# INTERNAL_REGULATORS.net
KiCad netlist of a schematic drawn in Altium Designer
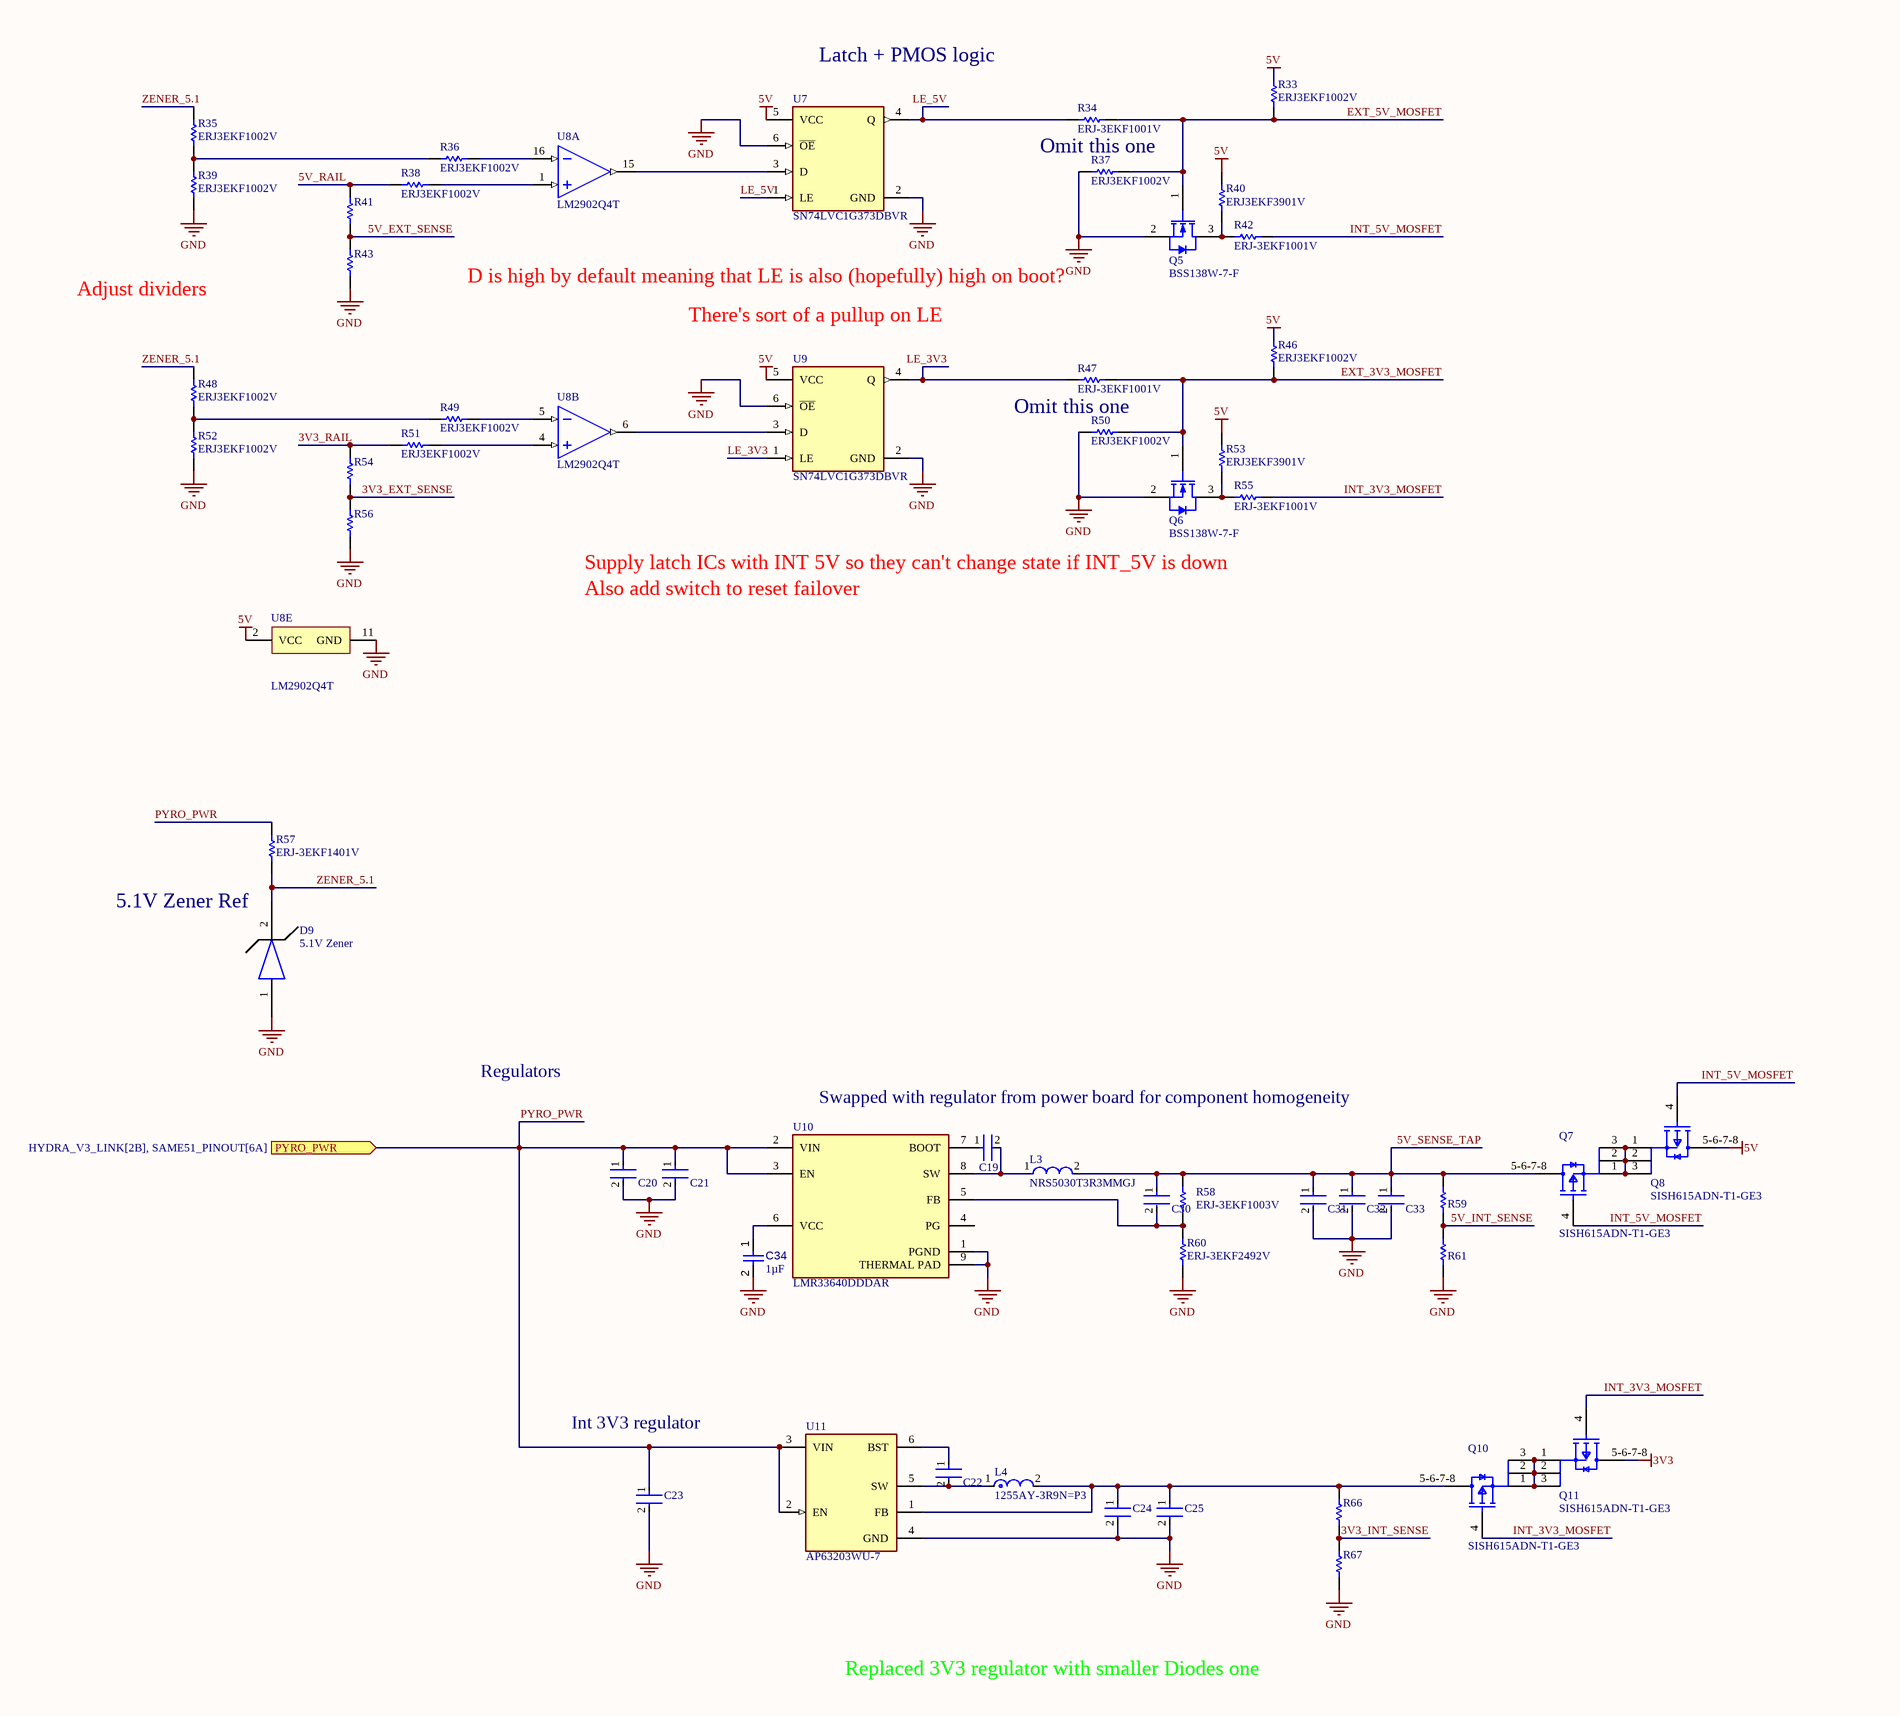
[diagram p0: INTERNAL_REGULATORS.SchDoc, left]
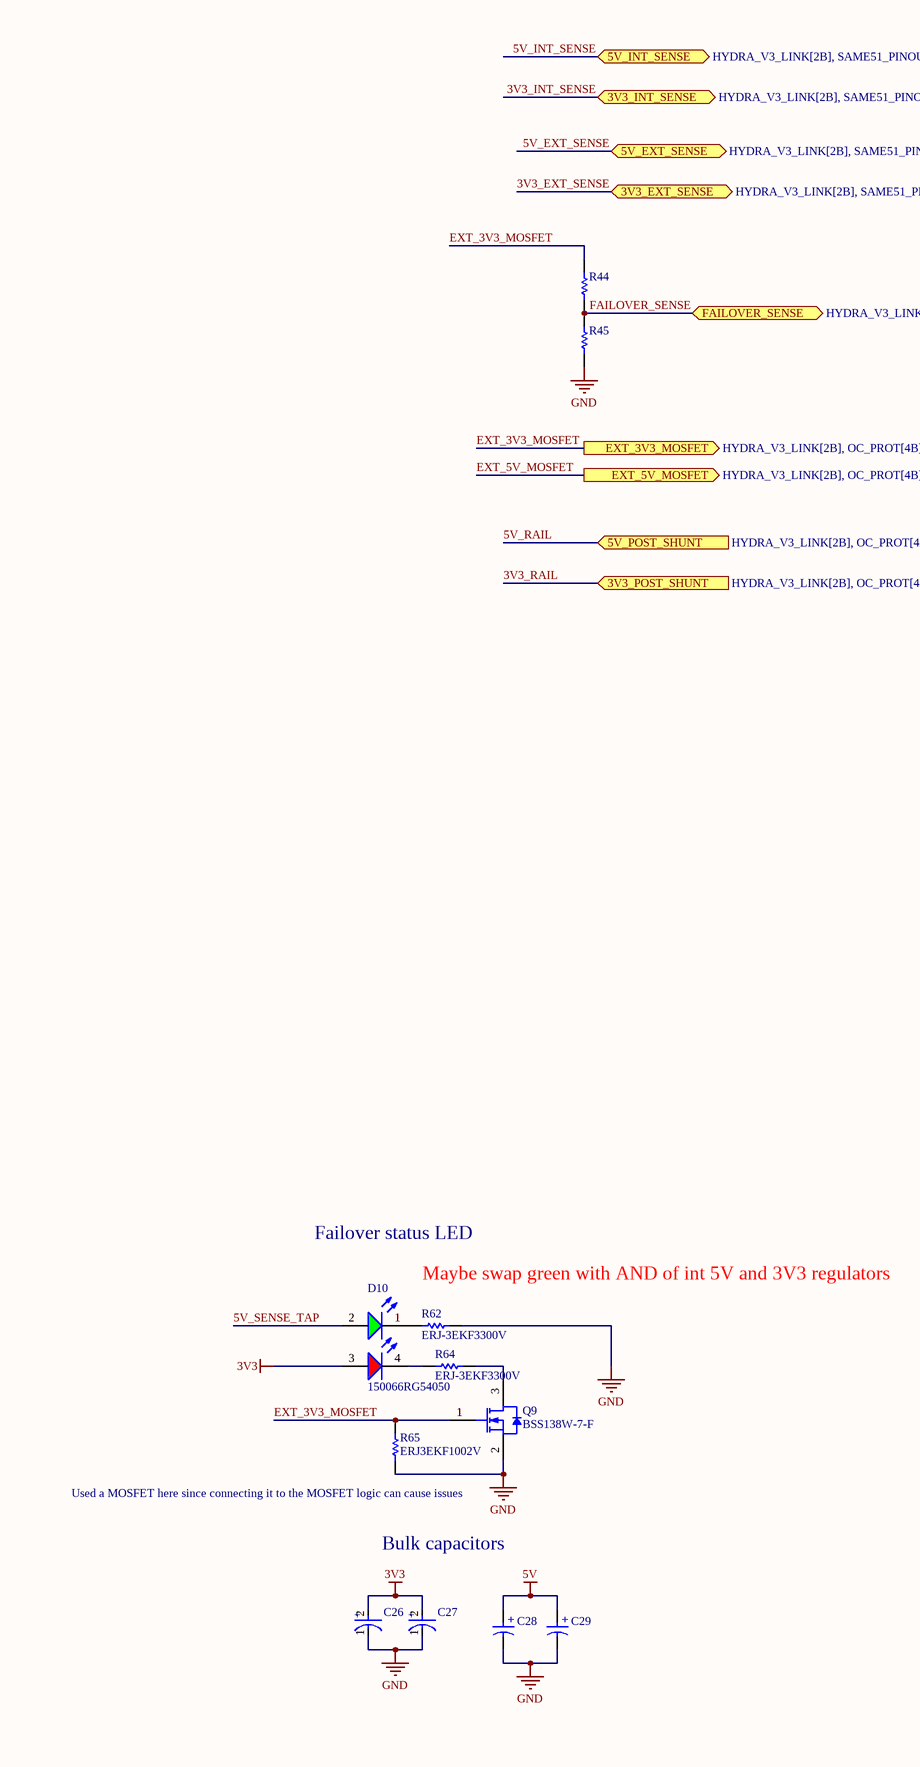
[diagram p1: INTERNAL_REGULATORS.SchDoc, right]

(export (version "E")
  (design (tool "Eeschema 10.0.6"))
  (components
    (comp (ref "C19")
      (value "C0402C104K8PACTU")
      (footprint "FP-C0402-BB-MFG")
      (description "CAP CER 0.1UF 10V X5R 0402")
      (fields (field (name "MANUFACTURER") "Kemet") (field (name "TOLERANCE") "0.1"))
      (libsource (lib "Altium Content Vault") (part "b4654b650e69147ec39a6b967a45e02"))
    )
    (comp (ref "C20")
      (value "CL10A106MA8NRNC")
      (footprint "FP-CL10-IPC_B")
      (libsource (lib "uORocketry Hardware") (part "b4654b650e69147ec39a6b967a45e02"))
    )
    (comp (ref "C21")
      (value "C0603C224M3RACTU")
      (footprint "FP-C0603C-CF-IPC_B")
      (libsource (lib "uORocketry Hardware") (part "b4654b650e69147ec39a6b967a45e02"))
    )
    (comp (ref "C22")
      (value "C0402C104K8PACTU")
      (footprint "FP-C0402-BB-MFG")
      (description "CAP CER 0.1UF 10V X5R 0402")
      (fields (field (name "MANUFACTURER") "Kemet") (field (name "TOLERANCE") "0.1"))
      (libsource (lib "Altium Content Vault") (part "b4654b650e69147ec39a6b967a45e02"))
    )
    (comp (ref "C23")
      (value "C0805C106K8PACTU")
      (footprint "FP-C0805C-DG-MFG")
      (description "CAP CER 10UF 10V X5R 0805")
      (fields (field (name "TOLERANCE") "10%") (field (name "MANUFACTURER") "Kemet"))
      (libsource (lib "Altium Content Vault") (part "11868f565c42a9108669ba33697ecf6"))
    )
    (comp (ref "C24")
      (value "GRM21BR61E226ME44L")
      (footprint "FP-GRM21B-0_2-e0_2_0_7-IPC_B")
      (description "Chip Multilayer Ceramic Capacitors for General Purpose, 0805, 22uF, X5R, 15%, 20%, 25V")
      (fields (field (name "TOLERANCE") "20%") (field (name "VOLTAGE") "25V"))
      (libsource (lib "Altium Content Vault") (part "b4654b650e69147ec39a6b967a45e02"))
    )
    (comp (ref "C25")
      (value "GRM21BR61E226ME44L")
      (footprint "FP-GRM21B-0_2-e0_2_0_7-IPC_B")
      (description "Chip Multilayer Ceramic Capacitors for General Purpose, 0805, 22uF, X5R, 15%, 20%, 25V")
      (fields (field (name "TOLERANCE") "20%") (field (name "VOLTAGE") "25V"))
      (libsource (lib "Altium Content Vault") (part "b4654b650e69147ec39a6b967a45e02"))
    )
    (comp (ref "C26")
      (value "6TPE120MAZB")
      (footprint "FP-POSCAP-B2-MFG")
      (description "Molded Tantalum Polymer Capacitor 120uF 20% 6.3V life 1000Hours SMD 1411")
      (fields (field (name "TOLERANCE") "20%") (field (name "VOLTAGE") "6.3V"))
      (libsource (lib "Altium Content Vault") (part "cf48714ba7e38822c1575c7ec0b6d1f"))
    )
    (comp (ref "C27")
      (value "6TPE120MAZB")
      (footprint "FP-POSCAP-B2-MFG")
      (description "Molded Tantalum Polymer Capacitor 120uF 20% 6.3V life 1000Hours SMD 1411")
      (fields (field (name "TOLERANCE") "20%") (field (name "VOLTAGE") "6.3V"))
      (libsource (lib "Altium Content Vault") (part "cf48714ba7e38822c1575c7ec0b6d1f"))
    )
    (comp (ref "C28")
      (value "875035119002")
      (footprint "WCAP-PHLE_L7.3W4.3H1.9")
      (description "875035119002 WCAP-PHLE Aluminum Polymer Capacitors")
      (libsource (lib "Altium Content Vault") (part "Capacitor_Polarized"))
    )
    (comp (ref "C29")
      (value "875035119002")
      (footprint "WCAP-PHLE_L7.3W4.3H1.9")
      (description "875035119002 WCAP-PHLE Aluminum Polymer Capacitors")
      (libsource (lib "Altium Content Vault") (part "Capacitor_Polarized"))
    )
    (comp (ref "C30")
      (value "C0603C101M3RACAUTO")
      (footprint "FP-C0603C-CF-IPC_B")
      (description "Ceramic Capacitor, Ceramic, 25V, 20% +Tol, 20% -Tol, X7R, 15% TC, 0.0001uF, Surface Mount, 0603")
      (libsource (lib "uORocketry Hardware") (part "b4654b650e69147ec39a6b967a45e02"))
    )
    (comp (ref "C31")
      (value "CL10A226MO7JZNC")
      (footprint "FP-CL10-IPC_B")
      (libsource (lib "uORocketry Hardware") (part "b4654b650e69147ec39a6b967a45e02"))
    )
    (comp (ref "C32")
      (value "CL10A226MO7JZNC")
      (footprint "FP-CL10-IPC_B")
      (libsource (lib "uORocketry Hardware") (part "b4654b650e69147ec39a6b967a45e02"))
    )
    (comp (ref "C33")
      (value "CL10A226MO7JZNC")
      (footprint "FP-CL10-IPC_B")
      (libsource (lib "uORocketry Hardware") (part "b4654b650e69147ec39a6b967a45e02"))
    )
    (comp (ref "C34")
      (value "1µF")
      (footprint "CAPC1608X90X35ML15T15")
      (description "Chip Capacitor, 1 uF, +/- 10%, 16 V, 0603 (1608 Metric)")
      (fields (field (name "TOLERANCE") "10%") (field (name "Comment") "Capacitor 1uF +/- 10% 16V 0603"))
      (libsource (lib "uORocketry Hardware") (part "CAP-NP-2"))
    )
    (comp (ref "D9")
      (value "5.1V Zener")
      (footprint "BZX884B5V1L-HG3-08-Footprint-1")
      (description "Diode Zener Single 5.1V 2% 300mW 2-Pin DFN1006 T/R")
      (libsource (lib "uORocketry Hardware") (part "BZX884B5V1L-HG3-08"))
    )
    (comp (ref "D10")
      (value "150066RG54050")
      (footprint "WL-SBCD_0606")
      (description "Led, Red/Grn, 180Mcd/230Mcd, 624Nm/525Nm Rohs Compliant: Yes")
      (libsource (lib "uORocketry Hardware") (part "WL-SBCD_0606_Red & Green"))
    )
    (comp (ref "L3")
      (value "NRS5030T3R3MMGJ")
      (footprint "FP-NRS5030-H_3_1-MFG")
      (description "Inductor Power Shielded Wirewound 3.3uH 20% 100KHz Ferrite 3A 39mΩ DCR T/R")
      (fields (field (name "TOLERANCE") "20%"))
      (libsource (lib "Altium Content Vault") (part "725321dda6339637d4d059423bc1c3c"))
    )
    (comp (ref "L4")
      (value "1255AY-3R9N=P3")
      (footprint "FP-DG6045C-MFG")
      (description "Shielded Wirewound Inductor 3.9uH 30% 4200mA 0.0264Ω SMD")
      (fields (field (name "TOLERANCE") "30%"))
      (libsource (lib "Altium Content Vault") (part "4cc4b267dca4c8e51f7102f422741d8"))
    )
    (comp (ref "Q5")
      (value "BSS138W-7-F")
      (footprint "DIOD-SOT323-3_V")
      (fields (field (name "MANUFACTURER") "DiodesIncorporated"))
      (libsource (lib "Altium Content Vault") (part "NEMOS-GSD-3"))
    )
    (comp (ref "Q6")
      (value "BSS138W-7-F")
      (footprint "DIOD-SOT323-3_V")
      (fields (field (name "MANUFACTURER") "DiodesIncorporated"))
      (libsource (lib "Altium Content Vault") (part "NEMOS-GSD-3"))
    )
    (comp (ref "Q7")
      (value "SISH615ADN-T1-GE3")
      (footprint "SISH615ADN-T1-GE3-Footprint-1")
      (description "Trans MOSFET P-CH 20V 22.1A 8-Pin PowerPAK 1212 EP T/R")
      (libsource (lib "uORocketry Hardware") (part "SISH615ADN-T1-GE3-Symbol-1"))
    )
    (comp (ref "Q8")
      (value "SISH615ADN-T1-GE3")
      (footprint "SISH615ADN-T1-GE3-Footprint-1")
      (description "Trans MOSFET P-CH 20V 22.1A 8-Pin PowerPAK 1212 EP T/R")
      (libsource (lib "uORocketry Hardware") (part "SISH615ADN-T1-GE3-Symbol-1"))
    )
    (comp (ref "Q9")
      (value "BSS138W-7-F")
      (footprint "DIOD-SOT323-3_V")
      (fields (field (name "MANUFACTURER") "DiodesIncorporated"))
      (libsource (lib "Altium Content Vault") (part "NEMOS-GSD-3"))
    )
    (comp (ref "Q10")
      (value "SISH615ADN-T1-GE3")
      (footprint "SISH615ADN-T1-GE3-Footprint-1")
      (description "Trans MOSFET P-CH 20V 22.1A 8-Pin PowerPAK 1212 EP T/R")
      (libsource (lib "uORocketry Hardware") (part "SISH615ADN-T1-GE3-Symbol-1"))
    )
    (comp (ref "Q11")
      (value "SISH615ADN-T1-GE3")
      (footprint "SISH615ADN-T1-GE3-Footprint-1")
      (description "Trans MOSFET P-CH 20V 22.1A 8-Pin PowerPAK 1212 EP T/R")
      (libsource (lib "uORocketry Hardware") (part "SISH615ADN-T1-GE3-Symbol-1"))
    )
    (comp (ref "R33")
      (value "ERJ3EKF1002V")
      (footprint "RESC1609X55X30LL15T15")
      (description "Chip Resistor, 10 KOhm, +/- 1%, 0.1 W, -55 to 155 degC, 0603 (1608 Metric), RoHS, Tape and Reel")
      (fields (field (name "TOLERANCE") "1%") (field (name "MANUFACTURER") "Panasonic"))
      (libsource (lib "Altium Content Vault") (part "RES-2"))
    )
    (comp (ref "R34")
      (value "ERJ-3EKF1001V")
      (footprint "RESC1608X55X30LL15T15")
      (fields (field (name "MANUFACTURER") "Panasonic"))
      (libsource (lib "Altium Content Vault") (part "RES"))
    )
    (comp (ref "R35")
      (value "ERJ3EKF1002V")
      (footprint "RESC1609X55X30LL15T15")
      (description "Chip Resistor, 10 KOhm, +/- 1%, 0.1 W, -55 to 155 degC, 0603 (1608 Metric), RoHS, Tape and Reel")
      (fields (field (name "TOLERANCE") "1%") (field (name "MANUFACTURER") "Panasonic"))
      (libsource (lib "Altium Content Vault") (part "RES-2"))
    )
    (comp (ref "R36")
      (value "ERJ3EKF1002V")
      (footprint "RESC1609X55X30LL15T15")
      (description "Chip Resistor, 10 KOhm, +/- 1%, 0.1 W, -55 to 155 degC, 0603 (1608 Metric), RoHS, Tape and Reel")
      (fields (field (name "TOLERANCE") "1%") (field (name "MANUFACTURER") "Panasonic"))
      (libsource (lib "Altium Content Vault") (part "RES-2"))
    )
    (comp (ref "R37")
      (value "ERJ3EKF1002V")
      (footprint "RESC1609X55X30LL15T15")
      (description "Chip Resistor, 10 KOhm, +/- 1%, 0.1 W, -55 to 155 degC, 0603 (1608 Metric), RoHS, Tape and Reel")
      (fields (field (name "TOLERANCE") "1%") (field (name "MANUFACTURER") "Panasonic"))
      (libsource (lib "Altium Content Vault") (part "RES-2"))
    )
    (comp (ref "R38")
      (value "ERJ3EKF1002V")
      (footprint "RESC1609X55X30LL15T15")
      (description "Chip Resistor, 10 KOhm, +/- 1%, 0.1 W, -55 to 155 degC, 0603 (1608 Metric), RoHS, Tape and Reel")
      (fields (field (name "TOLERANCE") "1%") (field (name "MANUFACTURER") "Panasonic"))
      (libsource (lib "Altium Content Vault") (part "RES-2"))
    )
    (comp (ref "R39")
      (value "ERJ3EKF1002V")
      (footprint "RESC1609X55X30LL15T15")
      (description "Chip Resistor, 10 KOhm, +/- 1%, 0.1 W, -55 to 155 degC, 0603 (1608 Metric), RoHS, Tape and Reel")
      (fields (field (name "TOLERANCE") "1%") (field (name "MANUFACTURER") "Panasonic"))
      (libsource (lib "Altium Content Vault") (part "RES-2"))
    )
    (comp (ref "R40")
      (value "ERJ3EKF3901V")
      (footprint "RESC1608X55X30ML15T15")
      (fields (field (name "MANUFACTURER") "Panasonic"))
      (libsource (lib "Altium Content Vault") (part "RES"))
    )
    (comp (ref "R41")
      (value "ERJ3EKF1002V")
      (footprint "RESC1609X55X30LL15T15")
      (description "Chip Resistor, 10 KOhm, +/- 1%, 0.1 W, -55 to 155 degC, 0603 (1608 Metric), RoHS, Tape and Reel")
      (fields (field (name "TOLERANCE") "1%") (field (name "MANUFACTURER") "Panasonic"))
      (libsource (lib "Altium Content Vault") (part "RES-2"))
    )
    (comp (ref "R42")
      (value "ERJ-3EKF1001V")
      (footprint "RESC1608X55X30LL15T15")
      (fields (field (name "MANUFACTURER") "Panasonic"))
      (libsource (lib "Altium Content Vault") (part "RES"))
    )
    (comp (ref "R43")
      (value "ERJ3EKF1002V")
      (footprint "RESC1609X55X30LL15T15")
      (description "Chip Resistor, 10 KOhm, +/- 1%, 0.1 W, -55 to 155 degC, 0603 (1608 Metric), RoHS, Tape and Reel")
      (fields (field (name "TOLERANCE") "1%") (field (name "MANUFACTURER") "Panasonic"))
      (libsource (lib "Altium Content Vault") (part "RES-2"))
    )
    (comp (ref "R44")
      (value "ERJ3EKF1002V")
      (footprint "RESC1609X55X30LL15T15")
      (description "Chip Resistor, 10 KOhm, +/- 1%, 0.1 W, -55 to 155 degC, 0603 (1608 Metric), RoHS, Tape and Reel")
      (fields (field (name "TOLERANCE") "1%") (field (name "MANUFACTURER") "Panasonic"))
      (libsource (lib "Altium Content Vault") (part "RES-2"))
    )
    (comp (ref "R45")
      (value "ERJ3EKF1002V")
      (footprint "RESC1609X55X30LL15T15")
      (description "Chip Resistor, 10 KOhm, +/- 1%, 0.1 W, -55 to 155 degC, 0603 (1608 Metric), RoHS, Tape and Reel")
      (fields (field (name "TOLERANCE") "1%") (field (name "MANUFACTURER") "Panasonic"))
      (libsource (lib "Altium Content Vault") (part "RES-2"))
    )
    (comp (ref "R46")
      (value "ERJ3EKF1002V")
      (footprint "RESC1609X55X30LL15T15")
      (description "Chip Resistor, 10 KOhm, +/- 1%, 0.1 W, -55 to 155 degC, 0603 (1608 Metric), RoHS, Tape and Reel")
      (fields (field (name "TOLERANCE") "1%") (field (name "MANUFACTURER") "Panasonic"))
      (libsource (lib "Altium Content Vault") (part "RES-2"))
    )
    (comp (ref "R47")
      (value "ERJ-3EKF1001V")
      (footprint "RESC1608X55X30LL15T15")
      (fields (field (name "MANUFACTURER") "Panasonic"))
      (libsource (lib "Altium Content Vault") (part "RES"))
    )
    (comp (ref "R48")
      (value "ERJ3EKF1002V")
      (footprint "RESC1609X55X30LL15T15")
      (description "Chip Resistor, 10 KOhm, +/- 1%, 0.1 W, -55 to 155 degC, 0603 (1608 Metric), RoHS, Tape and Reel")
      (fields (field (name "TOLERANCE") "1%") (field (name "MANUFACTURER") "Panasonic"))
      (libsource (lib "Altium Content Vault") (part "RES-2"))
    )
    (comp (ref "R49")
      (value "ERJ3EKF1002V")
      (footprint "RESC1609X55X30LL15T15")
      (description "Chip Resistor, 10 KOhm, +/- 1%, 0.1 W, -55 to 155 degC, 0603 (1608 Metric), RoHS, Tape and Reel")
      (fields (field (name "TOLERANCE") "1%") (field (name "MANUFACTURER") "Panasonic"))
      (libsource (lib "Altium Content Vault") (part "RES-2"))
    )
    (comp (ref "R50")
      (value "ERJ3EKF1002V")
      (footprint "RESC1609X55X30LL15T15")
      (description "Chip Resistor, 10 KOhm, +/- 1%, 0.1 W, -55 to 155 degC, 0603 (1608 Metric), RoHS, Tape and Reel")
      (fields (field (name "TOLERANCE") "1%") (field (name "MANUFACTURER") "Panasonic"))
      (libsource (lib "Altium Content Vault") (part "RES-2"))
    )
    (comp (ref "R51")
      (value "ERJ3EKF1002V")
      (footprint "RESC1609X55X30LL15T15")
      (description "Chip Resistor, 10 KOhm, +/- 1%, 0.1 W, -55 to 155 degC, 0603 (1608 Metric), RoHS, Tape and Reel")
      (fields (field (name "TOLERANCE") "1%") (field (name "MANUFACTURER") "Panasonic"))
      (libsource (lib "Altium Content Vault") (part "RES-2"))
    )
    (comp (ref "R52")
      (value "ERJ3EKF1002V")
      (footprint "RESC1609X55X30LL15T15")
      (description "Chip Resistor, 10 KOhm, +/- 1%, 0.1 W, -55 to 155 degC, 0603 (1608 Metric), RoHS, Tape and Reel")
      (fields (field (name "TOLERANCE") "1%") (field (name "MANUFACTURER") "Panasonic"))
      (libsource (lib "Altium Content Vault") (part "RES-2"))
    )
    (comp (ref "R53")
      (value "ERJ3EKF3901V")
      (footprint "RESC1608X55X30ML15T15")
      (fields (field (name "MANUFACTURER") "Panasonic"))
      (libsource (lib "Altium Content Vault") (part "RES"))
    )
    (comp (ref "R54")
      (value "ERJ3EKF1002V")
      (footprint "RESC1609X55X30LL15T15")
      (description "Chip Resistor, 10 KOhm, +/- 1%, 0.1 W, -55 to 155 degC, 0603 (1608 Metric), RoHS, Tape and Reel")
      (fields (field (name "TOLERANCE") "1%") (field (name "MANUFACTURER") "Panasonic"))
      (libsource (lib "Altium Content Vault") (part "RES-2"))
    )
    (comp (ref "R55")
      (value "ERJ-3EKF1001V")
      (footprint "RESC1608X55X30LL15T15")
      (fields (field (name "MANUFACTURER") "Panasonic"))
      (libsource (lib "Altium Content Vault") (part "RES"))
    )
    (comp (ref "R56")
      (value "ERJ3EKF1002V")
      (footprint "RESC1609X55X30LL15T15")
      (description "Chip Resistor, 10 KOhm, +/- 1%, 0.1 W, -55 to 155 degC, 0603 (1608 Metric), RoHS, Tape and Reel")
      (fields (field (name "TOLERANCE") "1%") (field (name "MANUFACTURER") "Panasonic"))
      (libsource (lib "Altium Content Vault") (part "RES-2"))
    )
    (comp (ref "R57")
      (value "ERJ-3EKF1401V")
      (footprint "RESC1608X55X30NL15T15")
      (fields (field (name "MANUFACTURER") "Panasonic"))
      (libsource (lib "Altium Content Vault") (part "RES"))
    )
    (comp (ref "R58")
      (value "ERJ-3EKF1003V")
      (footprint "RESC1608X55X30LL15T15")
      (description "Resistor Thick Film 0603 100K Ohm 1% 1/10W 100ppm/C Molded SMD Punched Carrier T/R")
      (libsource (lib "uORocketry Hardware") (part "RES"))
    )
    (comp (ref "R59")
      (value "ERJ3EKF1002V")
      (footprint "RESC1609X55X30LL15T15")
      (description "Chip Resistor, 10 KOhm, +/- 1%, 0.1 W, -55 to 155 degC, 0603 (1608 Metric), RoHS, Tape and Reel")
      (fields (field (name "TOLERANCE") "1%") (field (name "MANUFACTURER") "Panasonic"))
      (libsource (lib "Altium Content Vault") (part "RES-2"))
    )
    (comp (ref "R60")
      (value "ERJ-3EKF2492V")
      (footprint "RESC1608X55X30LL15T15")
      (fields (field (name "MANUFACTURER") "Panasonic"))
      (libsource (lib "Altium Content Vault") (part "RES"))
    )
    (comp (ref "R61")
      (value "ERJ3EKF1002V")
      (footprint "RESC1609X55X30LL15T15")
      (description "Chip Resistor, 10 KOhm, +/- 1%, 0.1 W, -55 to 155 degC, 0603 (1608 Metric), RoHS, Tape and Reel")
      (fields (field (name "TOLERANCE") "1%") (field (name "MANUFACTURER") "Panasonic"))
      (libsource (lib "Altium Content Vault") (part "RES-2"))
    )
    (comp (ref "R62")
      (value "ERJ-3EKF3300V")
      (footprint "RESC1608X55X30LL15T15")
      (description "Chip Resistor, 330 Ohm, +/- 1%, 0.1 W, -55 to 155 degC, 0603 (1608 Metric), RoHS, Tape and Reel")
      (libsource (lib "Altium Content Vault") (part "RES-2"))
    )
    (comp (ref "R64")
      (value "ERJ-3EKF3300V")
      (footprint "RESC1608X55X30LL15T15")
      (description "Chip Resistor, 330 Ohm, +/- 1%, 0.1 W, -55 to 155 degC, 0603 (1608 Metric), RoHS, Tape and Reel")
      (libsource (lib "Altium Content Vault") (part "RES-2"))
    )
    (comp (ref "R65")
      (value "ERJ3EKF1002V")
      (footprint "RESC1609X55X30LL15T15")
      (description "Chip Resistor, 10 KOhm, +/- 1%, 0.1 W, -55 to 155 degC, 0603 (1608 Metric), RoHS, Tape and Reel")
      (fields (field (name "TOLERANCE") "1%") (field (name "MANUFACTURER") "Panasonic"))
      (libsource (lib "Altium Content Vault") (part "RES-2"))
    )
    (comp (ref "R66")
      (value "ERJ3EKF1002V")
      (footprint "RESC1609X55X30LL15T15")
      (description "Chip Resistor, 10 KOhm, +/- 1%, 0.1 W, -55 to 155 degC, 0603 (1608 Metric), RoHS, Tape and Reel")
      (fields (field (name "TOLERANCE") "1%") (field (name "MANUFACTURER") "Panasonic"))
      (libsource (lib "Altium Content Vault") (part "RES-2"))
    )
    (comp (ref "R67")
      (value "ERJ3EKF1002V")
      (footprint "RESC1609X55X30LL15T15")
      (description "Chip Resistor, 10 KOhm, +/- 1%, 0.1 W, -55 to 155 degC, 0603 (1608 Metric), RoHS, Tape and Reel")
      (fields (field (name "TOLERANCE") "1%") (field (name "MANUFACTURER") "Panasonic"))
      (libsource (lib "Altium Content Vault") (part "RES-2"))
    )
    (comp (ref "U7")
      (value "SN74LVC1G373DBVR")
      (footprint "FP-DBV0006A-MFG")
      (description "IC LTCH D-TYP SGL 3-OUT SOT-23-6")
      (fields
        (field (name "OCTOPART") "https://octopart.com/sn74lvc1g373dbvr-texas+instruments-471164")
        (field (name "MANUFACTURER") "Texas Instruments")
      )
      (libsource (lib "Altium Content Vault") (part "914465a58c074970033cf31d7821f29"))
    )
    (comp (ref "U8")
      (value "LM2902Q4T")
      (footprint "LM2902Q4T-Footprint-1")
      (description "LM2902 Series 30 V 1.3 MHz Low-Power Quad Operational Amplifier - QFN-16 (3x3)")
      (libsource (lib "uORocketry Hardware") (part "LM2902Q4T"))
    )
    (comp (ref "U9")
      (value "SN74LVC1G373DBVR")
      (footprint "FP-DBV0006A-MFG")
      (description "IC LTCH D-TYP SGL 3-OUT SOT-23-6")
      (fields
        (field (name "OCTOPART") "https://octopart.com/sn74lvc1g373dbvr-texas+instruments-471164")
        (field (name "MANUFACTURER") "Texas Instruments")
      )
      (libsource (lib "Altium Content Vault") (part "914465a58c074970033cf31d7821f29"))
    )
    (comp (ref "U10")
      (value "LMR33640DDDAR")
      (footprint "FP-DDA0008J-IPC_A")
      (description "Switching Regulator, Current-mode, 4A, 1000kHz Switching Freq-Max, PDSO8")
      (libsource (lib "uORocketry Hardware") (part "0a006777bdb2f0bd68c221490016bf3"))
    )
    (comp (ref "U11")
      (value "AP63203WU-7")
      (footprint "FP-TSOT26-MFG")
      (description "IC REG BUCK 3.3V 2A TSOT26")
      (fields
        (field (name "MANUFACTURER") "Diodes Inc.")
        (field (name "OCTOPART") "https://octopart.com/ap63203wu-7-diodes+inc.-98099550")
      )
      (libsource (lib "Altium Content Vault") (part "0e61c2974d7114b43f01ef96ae2e524"))
    )
  )
  (nets
    (net (code "1") (name "/3V3_EXT_SENSE") (class "Default")
      (node (ref "R54") (pin "1") (pinfunction "1_1") (pintype "passive"))
      (node (ref "R56") (pin "2") (pinfunction "2_2") (pintype "passive"))
    )
    (net (code "2") (name "/3V3_INT_SENSE") (class "Default")
      (node (ref "R66") (pin "1") (pinfunction "1_1") (pintype "passive"))
      (node (ref "R67") (pin "2") (pinfunction "2_2") (pintype "passive"))
    )
    (net (code "3") (name "/3V3_RAIL") (class "Default")
      (node (ref "R51") (pin "2") (pinfunction "2_2") (pintype "passive"))
      (node (ref "R54") (pin "2") (pinfunction "2_2") (pintype "passive"))
    )
    (net (code "4") (name "/5V_EXT_SENSE") (class "Default")
      (node (ref "R41") (pin "1") (pinfunction "1_1") (pintype "passive"))
      (node (ref "R43") (pin "2") (pinfunction "2_2") (pintype "passive"))
    )
    (net (code "5") (name "/5V_INT_SENSE") (class "Default")
      (node (ref "R59") (pin "1") (pinfunction "1_1") (pintype "passive"))
      (node (ref "R61") (pin "2") (pinfunction "2_2") (pintype "passive"))
    )
    (net (code "6") (name "/5V_RAIL") (class "Default")
      (node (ref "R38") (pin "2") (pinfunction "2_2") (pintype "passive"))
      (node (ref "R41") (pin "2") (pinfunction "2_2") (pintype "passive"))
    )
    (net (code "7") (name "/5V_SENSE_TAP") (class "Default")
      (node (ref "C30") (pin "1") (pinfunction "1_1") (pintype "passive"))
      (node (ref "C31") (pin "1") (pinfunction "1_1") (pintype "passive"))
      (node (ref "C32") (pin "1") (pinfunction "1_1") (pintype "passive"))
      (node (ref "C33") (pin "1") (pinfunction "1_1") (pintype "passive"))
      (node (ref "D10") (pin "2") (pinfunction "A_2") (pintype "passive"))
      (node (ref "L3") (pin "2") (pinfunction "2_2") (pintype "passive"))
      (node (ref "Q7") (pin "5-6-7-8") (pinfunction "D_5-6-7-8") (pintype "passive"))
      (node (ref "R58") (pin "2") (pinfunction "2_2") (pintype "passive"))
      (node (ref "R59") (pin "2") (pinfunction "2_2") (pintype "passive"))
    )
    (net (code "8") (name "/EXT_3V3_MOSFET") (class "Default")
      (node (ref "Q6") (pin "1") (pinfunction "G_1") (pintype "passive"))
      (node (ref "Q9") (pin "1") (pinfunction "G_1") (pintype "passive"))
      (node (ref "R44") (pin "2") (pinfunction "2_2") (pintype "passive"))
      (node (ref "R46") (pin "2") (pinfunction "2_2") (pintype "passive"))
      (node (ref "R47") (pin "1") (pinfunction "1_1") (pintype "passive"))
      (node (ref "R50") (pin "1") (pinfunction "1_1") (pintype "passive"))
      (node (ref "R65") (pin "2") (pinfunction "2_2") (pintype "passive"))
    )
    (net (code "9") (name "/EXT_5V_MOSFET") (class "Default")
      (node (ref "Q5") (pin "1") (pinfunction "G_1") (pintype "passive"))
      (node (ref "R33") (pin "2") (pinfunction "2_2") (pintype "passive"))
      (node (ref "R34") (pin "1") (pinfunction "1_1") (pintype "passive"))
      (node (ref "R37") (pin "1") (pinfunction "1_1") (pintype "passive"))
    )
    (net (code "10") (name "/FAILOVER_SENSE") (class "Default")
      (node (ref "R44") (pin "1") (pinfunction "1_1") (pintype "passive"))
      (node (ref "R45") (pin "2") (pinfunction "2_2") (pintype "passive"))
    )
    (net (code "11") (name "/INT_3V3_MOSFET") (class "Default")
      (node (ref "Q10") (pin "4") (pinfunction "G_4") (pintype "passive"))
      (node (ref "Q11") (pin "4") (pinfunction "G_4") (pintype "passive"))
      (node (ref "R55") (pin "2") (pinfunction "2_2") (pintype "passive"))
    )
    (net (code "12") (name "/INT_5V_MOSFET") (class "Default")
      (node (ref "Q7") (pin "4") (pinfunction "G_4") (pintype "passive"))
      (node (ref "Q8") (pin "4") (pinfunction "G_4") (pintype "passive"))
      (node (ref "R42") (pin "2") (pinfunction "2_2") (pintype "passive"))
    )
    (net (code "13") (name "/LE_3V3") (class "Default")
      (node (ref "R47") (pin "2") (pinfunction "2_2") (pintype "passive"))
      (node (ref "U9") (pin "1") (pinfunction "LE_1") (pintype "input"))
      (node (ref "U9") (pin "4") (pinfunction "Q_4") (pintype "output"))
    )
    (net (code "14") (name "/LE_5V") (class "Default")
      (node (ref "R34") (pin "2") (pinfunction "2_2") (pintype "passive"))
      (node (ref "U7") (pin "1") (pinfunction "LE_1") (pintype "input"))
      (node (ref "U7") (pin "4") (pinfunction "Q_4") (pintype "output"))
    )
    (net (code "15") (name "/PYRO_PWR") (class "Default")
      (node (ref "C20") (pin "1") (pinfunction "1_1") (pintype "passive"))
      (node (ref "C21") (pin "1") (pinfunction "1_1") (pintype "passive"))
      (node (ref "C23") (pin "1") (pinfunction "1_1") (pintype "passive"))
      (node (ref "R57") (pin "2") (pinfunction "2_2") (pintype "passive"))
      (node (ref "U10") (pin "2") (pinfunction "VIN_2") (pintype "passive"))
      (node (ref "U10") (pin "3") (pinfunction "EN_3") (pintype "passive"))
      (node (ref "U11") (pin "2") (pinfunction "EN_2") (pintype "input"))
      (node (ref "U11") (pin "3") (pinfunction "VIN_3") (pintype "power_in"))
    )
    (net (code "16") (name "/ZENER_5.1") (class "Default")
      (node (ref "D9") (pin "2") (pinfunction "2_2") (pintype "passive"))
      (node (ref "R35") (pin "1") (pinfunction "1_1") (pintype "passive"))
      (node (ref "R48") (pin "1") (pinfunction "1_1") (pintype "passive"))
      (node (ref "R57") (pin "1") (pinfunction "1_1") (pintype "passive"))
    )
    (net (code "17") (name "3V3") (class "Default")
      (node (ref "C26") (pin "2") (pinfunction "A_2") (pintype "passive"))
      (node (ref "C27") (pin "2") (pinfunction "A_2") (pintype "passive"))
      (node (ref "D10") (pin "3") (pinfunction "A_3") (pintype "passive"))
      (node (ref "Q11") (pin "5-6-7-8") (pinfunction "D_5-6-7-8") (pintype "passive"))
    )
    (net (code "18") (name "5V") (class "Default")
      (node (ref "C28") (pin "1") (pinfunction "P_1") (pintype "passive"))
      (node (ref "C29") (pin "1") (pinfunction "P_1") (pintype "passive"))
      (node (ref "Q8") (pin "5-6-7-8") (pinfunction "D_5-6-7-8") (pintype "passive"))
      (node (ref "R33") (pin "1") (pinfunction "1_1") (pintype "passive"))
      (node (ref "R40") (pin "2") (pinfunction "2_2") (pintype "passive"))
      (node (ref "R46") (pin "1") (pinfunction "1_1") (pintype "passive"))
      (node (ref "R53") (pin "2") (pinfunction "2_2") (pintype "passive"))
      (node (ref "U7") (pin "5") (pinfunction "VCC_5") (pintype "power_in"))
      (node (ref "U8") (pin "2") (pinfunction "VCC_2") (pintype "power_in"))
      (node (ref "U9") (pin "5") (pinfunction "VCC_5") (pintype "power_in"))
    )
    (net (code "19") (name "GND") (class "Default")
      (node (ref "C20") (pin "2") (pinfunction "2_2") (pintype "passive"))
      (node (ref "C21") (pin "2") (pinfunction "2_2") (pintype "passive"))
      (node (ref "C23") (pin "2") (pinfunction "2_2") (pintype "passive"))
      (node (ref "C24") (pin "2") (pinfunction "2_2") (pintype "passive"))
      (node (ref "C25") (pin "2") (pinfunction "2_2") (pintype "passive"))
      (node (ref "C26") (pin "1") (pinfunction "C_1") (pintype "passive"))
      (node (ref "C27") (pin "1") (pinfunction "C_1") (pintype "passive"))
      (node (ref "C28") (pin "2") (pinfunction "N_2") (pintype "passive"))
      (node (ref "C29") (pin "2") (pinfunction "N_2") (pintype "passive"))
      (node (ref "C31") (pin "2") (pinfunction "2_2") (pintype "passive"))
      (node (ref "C32") (pin "2") (pinfunction "2_2") (pintype "passive"))
      (node (ref "C33") (pin "2") (pinfunction "2_2") (pintype "passive"))
      (node (ref "C34") (pin "2") (pinfunction "2_2") (pintype "passive"))
      (node (ref "D9") (pin "1") (pinfunction "1_1") (pintype "passive"))
      (node (ref "Q5") (pin "2") (pinfunction "S_2") (pintype "passive"))
      (node (ref "Q6") (pin "2") (pinfunction "S_2") (pintype "passive"))
      (node (ref "Q9") (pin "2") (pinfunction "S_2") (pintype "passive"))
      (node (ref "R37") (pin "2") (pinfunction "2_2") (pintype "passive"))
      (node (ref "R39") (pin "2") (pinfunction "2_2") (pintype "passive"))
      (node (ref "R43") (pin "1") (pinfunction "1_1") (pintype "passive"))
      (node (ref "R45") (pin "1") (pinfunction "1_1") (pintype "passive"))
      (node (ref "R50") (pin "2") (pinfunction "2_2") (pintype "passive"))
      (node (ref "R52") (pin "2") (pinfunction "2_2") (pintype "passive"))
      (node (ref "R56") (pin "1") (pinfunction "1_1") (pintype "passive"))
      (node (ref "R60") (pin "1") (pinfunction "1_1") (pintype "passive"))
      (node (ref "R61") (pin "1") (pinfunction "1_1") (pintype "passive"))
      (node (ref "R62") (pin "2") (pinfunction "2_2") (pintype "passive"))
      (node (ref "R65") (pin "1") (pinfunction "1_1") (pintype "passive"))
      (node (ref "R67") (pin "1") (pinfunction "1_1") (pintype "passive"))
      (node (ref "U10") (pin "1") (pinfunction "PGND_1") (pintype "power_in"))
      (node (ref "U10") (pin "9") (pinfunction "THERMAL_PAD_9") (pintype "power_in"))
      (node (ref "U11") (pin "4") (pinfunction "GND_4") (pintype "power_in"))
      (node (ref "U7") (pin "2") (pinfunction "GND_2") (pintype "power_in"))
      (node (ref "U7") (pin "6") (pinfunction "~{OE}_6") (pintype "input"))
      (node (ref "U8") (pin "11") (pinfunction "GND_11") (pintype "power_in"))
      (node (ref "U9") (pin "2") (pinfunction "GND_2") (pintype "power_in"))
      (node (ref "U9") (pin "6") (pinfunction "~{OE}_6") (pintype "input"))
    )
    (net (code "20") (name "Net-(D10-K-Pad1)") (class "Default")
      (node (ref "D10") (pin "1") (pinfunction "K_1") (pintype "passive"))
      (node (ref "R62") (pin "1") (pinfunction "1_1") (pintype "passive"))
    )
    (net (code "21") (name "Net-(D10-K-Pad4)") (class "Default")
      (node (ref "D10") (pin "4") (pinfunction "K_4") (pintype "passive"))
      (node (ref "R64") (pin "1") (pinfunction "1_1") (pintype "passive"))
    )
    (net (code "22") (name "Net-(Q5-D)") (class "Default")
      (node (ref "Q5") (pin "3") (pinfunction "D_3") (pintype "passive"))
      (node (ref "R40") (pin "1") (pinfunction "1_1") (pintype "passive"))
      (node (ref "R42") (pin "1") (pinfunction "1_1") (pintype "passive"))
    )
    (net (code "23") (name "Net-(Q6-D)") (class "Default")
      (node (ref "Q6") (pin "3") (pinfunction "D_3") (pintype "passive"))
      (node (ref "R53") (pin "1") (pinfunction "1_1") (pintype "passive"))
      (node (ref "R55") (pin "1") (pinfunction "1_1") (pintype "passive"))
    )
    (net (code "24") (name "Net-(Q7-S-Pad1)") (class "Default")
      (node (ref "Q7") (pin "1") (pinfunction "S_1") (pintype "passive"))
      (node (ref "Q7") (pin "2") (pinfunction "S_2") (pintype "passive"))
      (node (ref "Q7") (pin "3") (pinfunction "S_3") (pintype "passive"))
      (node (ref "Q8") (pin "1") (pinfunction "S_1") (pintype "passive"))
      (node (ref "Q8") (pin "2") (pinfunction "S_2") (pintype "passive"))
      (node (ref "Q8") (pin "3") (pinfunction "S_3") (pintype "passive"))
    )
    (net (code "25") (name "Net-(Q9-D)") (class "Default")
      (node (ref "Q9") (pin "3") (pinfunction "D_3") (pintype "passive"))
      (node (ref "R64") (pin "2") (pinfunction "2_2") (pintype "passive"))
    )
    (net (code "26") (name "Net-(Q10-D)") (class "Default")
      (node (ref "C24") (pin "1") (pinfunction "1_1") (pintype "passive"))
      (node (ref "C25") (pin "1") (pinfunction "1_1") (pintype "passive"))
      (node (ref "L4") (pin "2") (pinfunction "2_2") (pintype "passive"))
      (node (ref "Q10") (pin "5-6-7-8") (pinfunction "D_5-6-7-8") (pintype "passive"))
      (node (ref "R66") (pin "2") (pinfunction "2_2") (pintype "passive"))
      (node (ref "U11") (pin "1") (pinfunction "FB_1") (pintype "passive"))
    )
    (net (code "27") (name "Net-(Q10-S-Pad1)") (class "Default")
      (node (ref "Q10") (pin "1") (pinfunction "S_1") (pintype "passive"))
      (node (ref "Q10") (pin "2") (pinfunction "S_2") (pintype "passive"))
      (node (ref "Q10") (pin "3") (pinfunction "S_3") (pintype "passive"))
      (node (ref "Q11") (pin "1") (pinfunction "S_1") (pintype "passive"))
      (node (ref "Q11") (pin "2") (pinfunction "S_2") (pintype "passive"))
      (node (ref "Q11") (pin "3") (pinfunction "S_3") (pintype "passive"))
    )
    (net (code "28") (name "Net-(R35-Pad2)") (class "Default")
      (node (ref "R35") (pin "2") (pinfunction "2_2") (pintype "passive"))
      (node (ref "R36") (pin "2") (pinfunction "2_2") (pintype "passive"))
      (node (ref "R39") (pin "1") (pinfunction "1_1") (pintype "passive"))
    )
    (net (code "29") (name "Net-(R48-Pad2)") (class "Default")
      (node (ref "R48") (pin "2") (pinfunction "2_2") (pintype "passive"))
      (node (ref "R49") (pin "2") (pinfunction "2_2") (pintype "passive"))
      (node (ref "R52") (pin "1") (pinfunction "1_1") (pintype "passive"))
    )
    (net (code "30") (name "Net-(U7-D)") (class "Default")
      (node (ref "U7") (pin "3") (pinfunction "D_3") (pintype "input"))
      (node (ref "U8") (pin "15") (pinfunction "1OUT_15") (pintype "output"))
    )
    (net (code "31") (name "Net-(U8A-1IN+)") (class "Default")
      (node (ref "R38") (pin "1") (pinfunction "1_1") (pintype "passive"))
      (node (ref "U8") (pin "1") (pinfunction "1IN+_1") (pintype "input"))
    )
    (net (code "32") (name "Net-(U8A-1IN-)") (class "Default")
      (node (ref "R36") (pin "1") (pinfunction "1_1") (pintype "passive"))
      (node (ref "U8") (pin "16") (pinfunction "1IN-_16") (pintype "input"))
    )
    (net (code "33") (name "Net-(U8B-2IN+)") (class "Default")
      (node (ref "R51") (pin "1") (pinfunction "1_1") (pintype "passive"))
      (node (ref "U8") (pin "4") (pinfunction "2IN+_4") (pintype "input"))
    )
    (net (code "34") (name "Net-(U8B-2IN-)") (class "Default")
      (node (ref "R49") (pin "1") (pinfunction "1_1") (pintype "passive"))
      (node (ref "U8") (pin "5") (pinfunction "2IN-_5") (pintype "input"))
    )
    (net (code "35") (name "Net-(U8B-2OUT)") (class "Default")
      (node (ref "U8") (pin "6") (pinfunction "2OUT_6") (pintype "output"))
      (node (ref "U9") (pin "3") (pinfunction "D_3") (pintype "input"))
    )
    (net (code "36") (name "Net-(U10-BOOT)") (class "Default")
      (node (ref "C19") (pin "1") (pinfunction "1_1") (pintype "passive"))
      (node (ref "U10") (pin "7") (pinfunction "BOOT_7") (pintype "passive"))
    )
    (net (code "37") (name "Net-(U10-FB)") (class "Default")
      (node (ref "C30") (pin "2") (pinfunction "2_2") (pintype "passive"))
      (node (ref "R58") (pin "1") (pinfunction "1_1") (pintype "passive"))
      (node (ref "R60") (pin "2") (pinfunction "2_2") (pintype "passive"))
      (node (ref "U10") (pin "5") (pinfunction "FB_5") (pintype "passive"))
    )
    (net (code "38") (name "Net-(U10-SW)") (class "Default")
      (node (ref "C19") (pin "2") (pinfunction "2_2") (pintype "passive"))
      (node (ref "L3") (pin "1") (pinfunction "1_1") (pintype "passive"))
      (node (ref "U10") (pin "8") (pinfunction "SW_8") (pintype "passive"))
    )
    (net (code "39") (name "Net-(U10-VCC)") (class "Default")
      (node (ref "C34") (pin "1") (pinfunction "1_1") (pintype "passive"))
      (node (ref "U10") (pin "6") (pinfunction "VCC_6") (pintype "passive"))
    )
    (net (code "40") (name "Net-(U11-BST)") (class "Default")
      (node (ref "C22") (pin "1") (pinfunction "1_1") (pintype "passive"))
      (node (ref "U11") (pin "6") (pinfunction "BST_6") (pintype "passive"))
    )
    (net (code "41") (name "Net-(U11-SW)") (class "Default")
      (node (ref "C22") (pin "2") (pinfunction "2_2") (pintype "passive"))
      (node (ref "L4") (pin "1") (pinfunction "1_1") (pintype "passive"))
      (node (ref "U11") (pin "5") (pinfunction "SW_5") (pintype "passive"))
    )
    (net (code "42") (name "unconnected-(U10-PG-Pad4)") (class "Default")
      (node (ref "U10") (pin "4") (pinfunction "PG_4") (pintype "open_collector"))
    )
  )
)
